# ProDoc_ChisFlash-Pichu.net
KiCad netlist of a schematic drawn in EasyEDA Pro
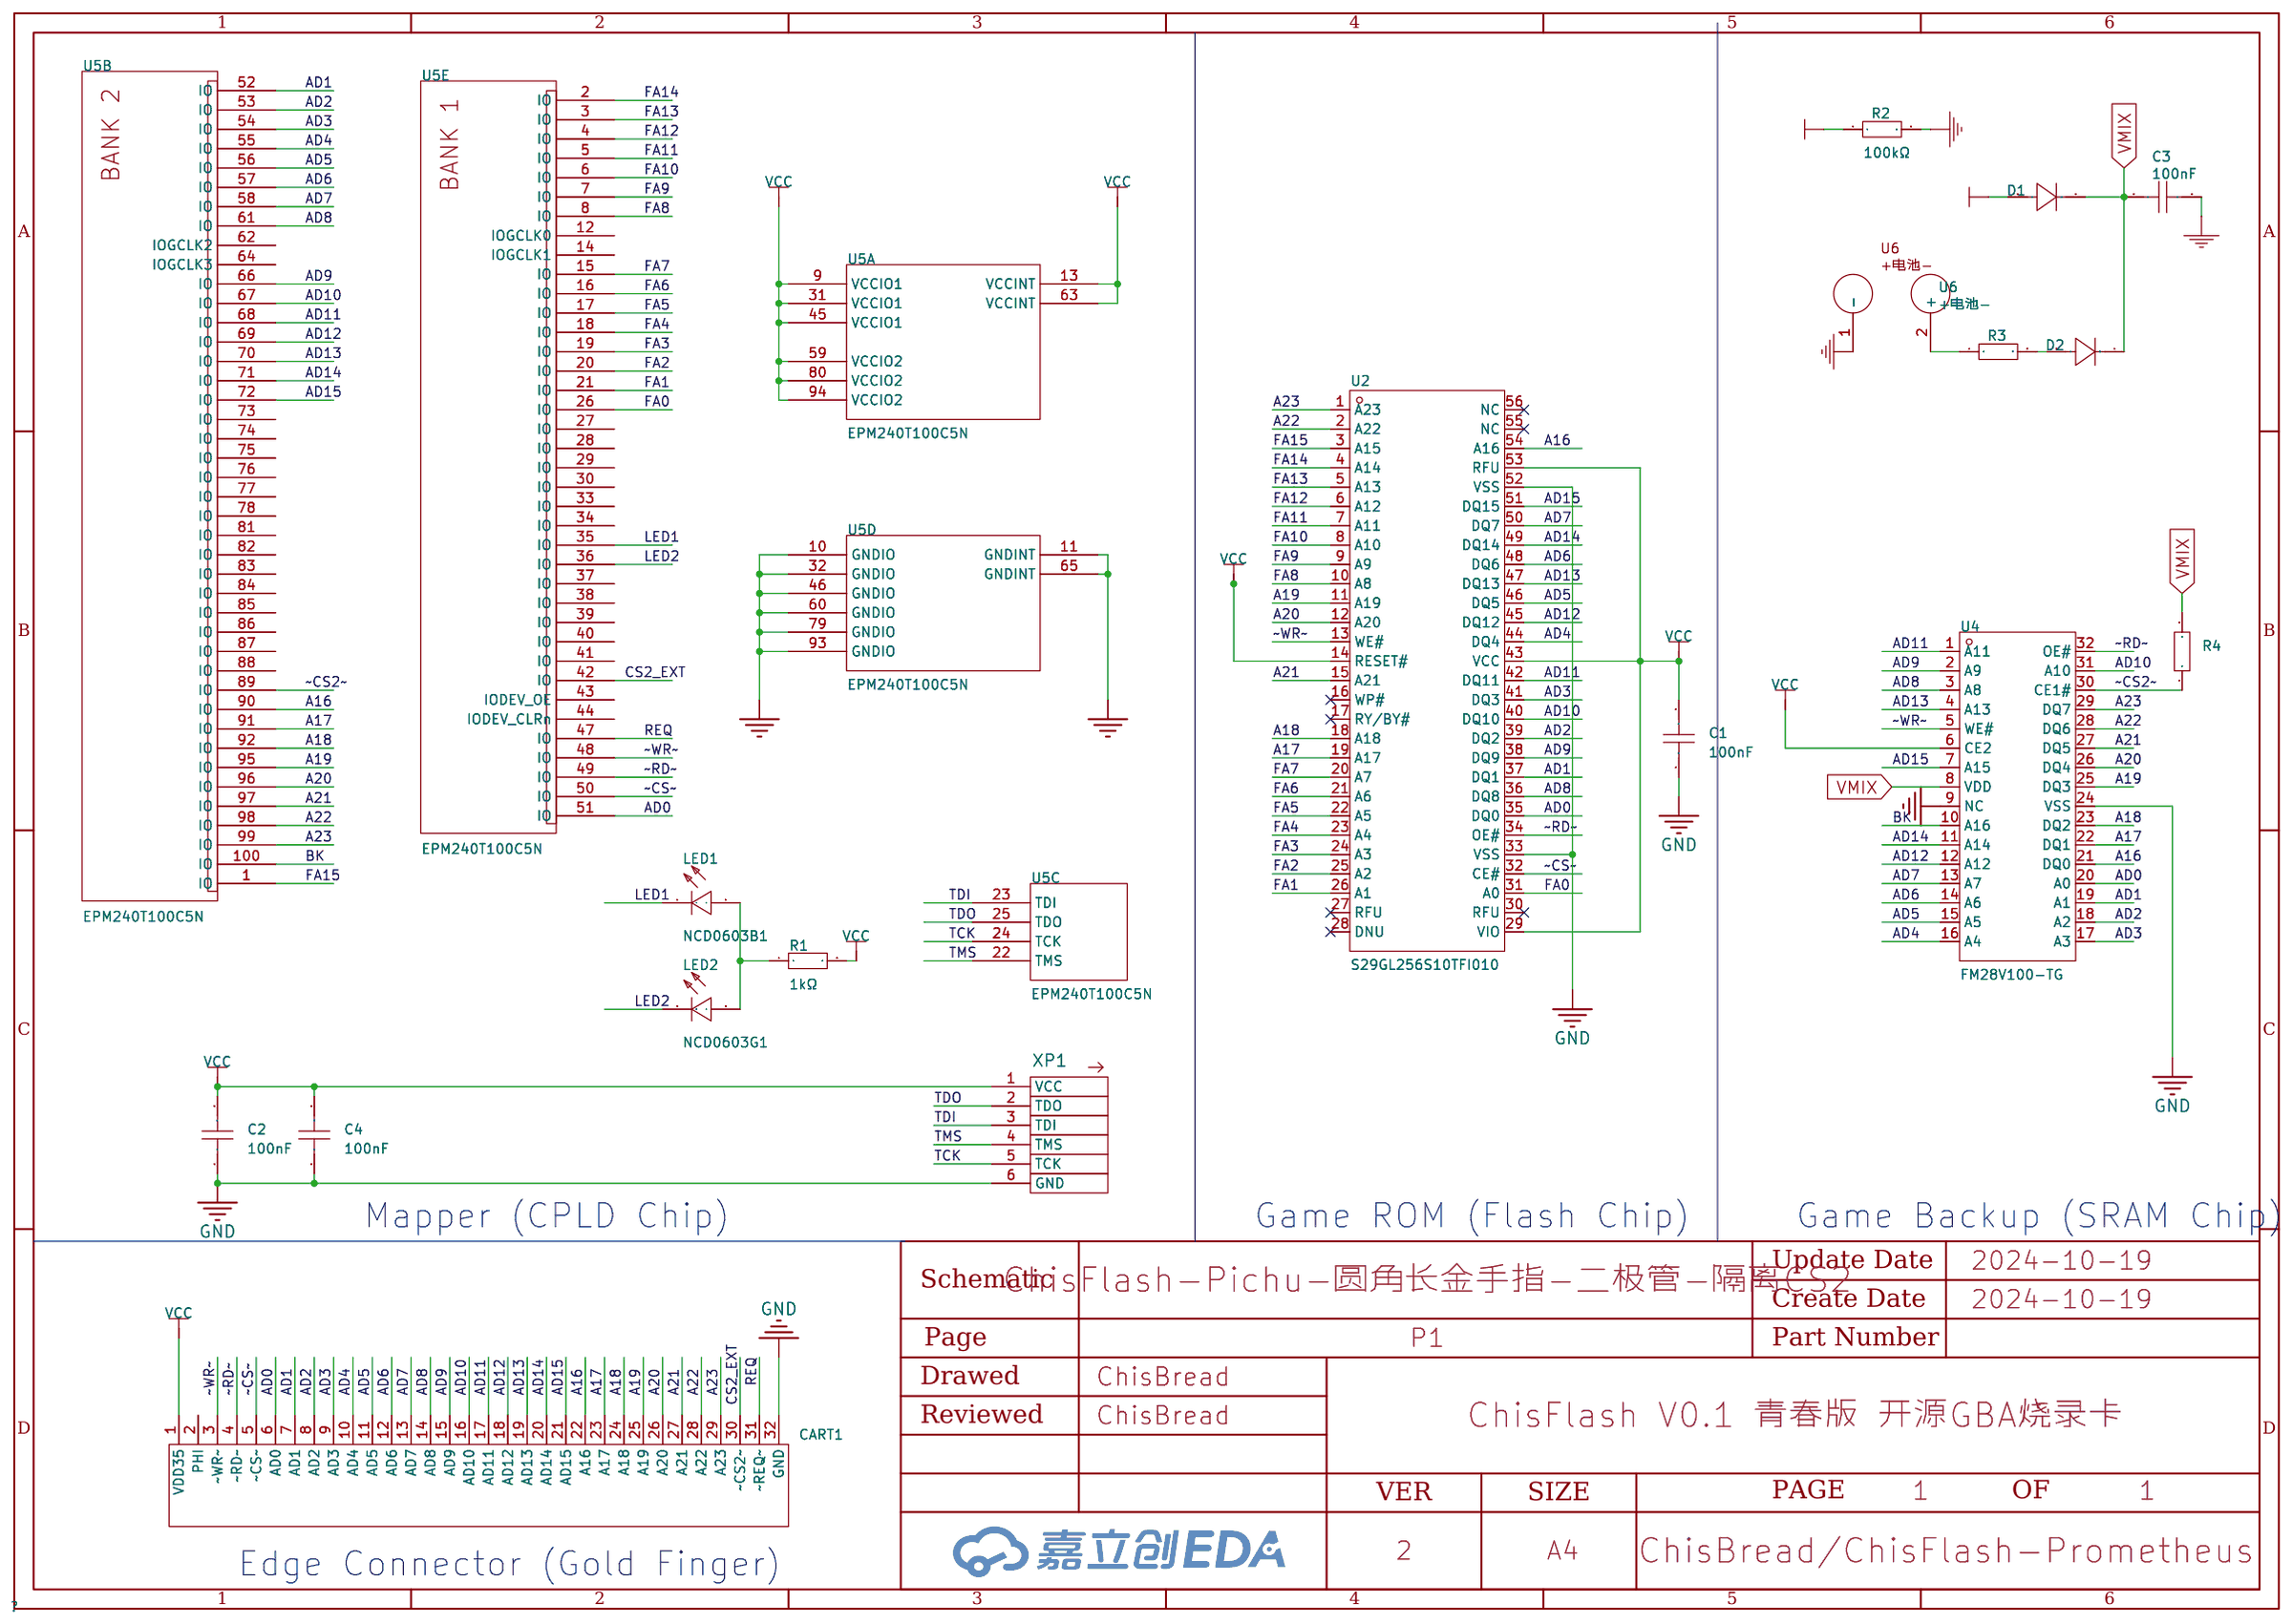
[diagram p0: schematic sheet]

(export (version "E")
  (design (tool "Eeschema 10.0.6"))
  (components
    (comp (ref "C1")
      (value "100nF")
      (footprint "easyedapro:C0603")
      (libsource (lib "easyedapro") (part "CapAcitance"))
    )
    (comp (ref "C2")
      (value "100nF")
      (footprint "easyedapro:C0603")
      (libsource (lib "easyedapro") (part "CapAcitance"))
    )
    (comp (ref "C3")
      (value "100nF")
      (footprint "easyedapro:C0603")
      (description "容值:100nF;精度:±10%;额定电压:50V;材质(温度系数):X7R;")
      (fields
        (field (name "Manufacturer Part") "CGA0603X7R104K500JT")
        (field (name "Manufacturer") "HRE(芯声)")
      )
      (libsource (lib "easyedapro") (part "CGA0603X7R104K500JT"))
    )
    (comp (ref "C4")
      (value "100nF")
      (footprint "easyedapro:C0603")
      (libsource (lib "easyedapro") (part "CapAcitance"))
    )
    (comp (ref "CART1")
      (value "~")
      (footprint "easyedapro:GBA卡带金手指")
      (description "GBA卡带金手指")
      (libsource (lib "easyedapro") (part "GBA卡带金手指"))
    )
    (comp (ref "D1")
      (value "1N4148WS")
      (footprint "easyedapro:SOD-323_L1.8-W1.3-LS2.5-RD")
      (description "二极管配置:独立式;正向压降(Vf):1.25V@150mA;直流反向耐压(Vr):100V;平均整流电流(Io):300mA;功率:400mW;反向恢复时间(trr):8ns;")
      (fields (field (name "Manufacturer") "JSMSEMI(杰盛微)"))
      (libsource (lib "easyedapro") (part "1N4148WS_C917117"))
    )
    (comp (ref "D2")
      (value "1N4148WS")
      (footprint "easyedapro:SOD-323_L1.8-W1.3-LS2.5-RD")
      (description "二极管配置:独立式;正向压降(Vf):1.25V@150mA;直流反向耐压(Vr):100V;平均整流电流(Io):300mA;功率:400mW;反向恢复时间(trr):8ns;")
      (fields (field (name "Manufacturer") "JSMSEMI(杰盛微)"))
      (libsource (lib "easyedapro") (part "1N4148WS_C917117"))
    )
    (comp (ref "LED1")
      (value "NCD0603B1")
      (footprint "easyedapro:LED0603-RD")
      (fields (field (name "Manufacturer") "国星光电"))
      (libsource (lib "easyedapro") (part "FC-DA1608BK-470H10"))
    )
    (comp (ref "LED2")
      (value "NCD0603G1")
      (footprint "easyedapro:LED0603-RD")
      (fields (field (name "Manufacturer") "国星光电"))
      (libsource (lib "easyedapro") (part "FC-D1608UGK-520D10"))
    )
    (comp (ref "R1")
      (value "1kΩ")
      (footprint "easyedapro:R0603")
      (description "电阻类型:厚膜电阻;阻值:1kΩ;精度:±1%;功率:100mW;最大工作电压:75V;温度系数:±100ppm/°C;")
      (fields
        (field (name "Manufacturer Part") "0603WAF1001T5E")
        (field (name "Manufacturer") "UNI-ROYAL(厚声)")
      )
      (libsource (lib "easyedapro") (part "0603WAF1001T5E"))
    )
    (comp (ref "R2")
      (value "100kΩ")
      (footprint "easyedapro:R0603")
      (description "电阻类型:厚膜电阻;阻值:100kΩ;精度:±1%;功率:100mW;最大工作电压:75V;温度系数:±100ppm/°C;")
      (fields
        (field (name "Manufacturer Part") "0603WAF1003T5E")
        (field (name "Manufacturer") "UNI-ROYAL(厚声)")
      )
      (libsource (lib "easyedapro") (part "0603WAF1003T5E"))
    )
    (comp (ref "R3")
      (value "10kΩ")
      (footprint "easyedapro:R0603")
      (description "电阻类型:厚膜电阻;阻值:10kΩ;精度:±1%;功率:100mW;最大工作电压:75V;温度系数:±100ppm/°C;")
      (fields
        (field (name "Manufacturer Part") "0603WAF1002T5E")
        (field (name "Manufacturer") "UNI-ROYAL(厚声)")
      )
      (libsource (lib "easyedapro") (part "0603WAF1002T5E"))
    )
    (comp (ref "R4")
      (value "10kΩ")
      (footprint "easyedapro:R0603")
      (description "电阻类型:厚膜电阻;阻值:10kΩ;精度:±1%;功率:100mW;最大工作电压:75V;温度系数:±100ppm/°C;")
      (fields
        (field (name "Manufacturer Part") "0603WAF1002T5E")
        (field (name "Manufacturer") "UNI-ROYAL(厚声)")
      )
      (libsource (lib "easyedapro") (part "0603WAF1002T5E"))
    )
    (comp (ref "U2")
      (value "S29GL256S10TFI010")
      (footprint "easyedapro:TSOP-56_L18.4-W14.0-P0.50-LS20.0-TL")
      (fields (field (name "Manufacturer") "SPANSION(飞索)"))
      (libsource (lib "easyedapro") (part "S29GL256S10TFI010"))
    )
    (comp (ref "U4")
      (value "FM28V100-TG")
      (fields (field (name "Manufacturer") "CYPRESS(赛普拉斯)"))
      (libsource (lib "easyedapro") (part "FM28V100-TG_C2959453"))
    )
    (comp (ref "U5")
      (value "EPM240T100C5N")
      (footprint "easyedapro:TQFP-100_L14.0-W14.0-P0.50-LS16.0-BL")
      (description "类型:其它PLD;逻辑门数量:-;逻辑单元数:-;逻辑阵列块数:240;")
      (fields (field (name "Manufacturer") "Intel/Altera"))
      (libsource (lib "easyedapro") (part "EPM240T100C5N"))
    )
    (comp (ref "U6")
      (value "+电池-")
      (footprint "easyedapro:电池2")
      (libsource (lib "easyedapro") (part "GBA烧录卡电池"))
    )
    (comp (ref "XP1")
      (value "JTAG")
      (footprint "easyedapro:HDR-TH_6P-P1.27-V-M-1")
      (libsource (lib "easyedapro") (part "jtag"))
    )
  )
  (nets
    (net (code "1") (name "/A16") (class "Default")
      (node (ref "CART1") (pin "22") (pinfunction "A16_22") (pintype "input"))
      (node (ref "U2") (pin "54") (pinfunction "A16_54") (pintype "input"))
      (node (ref "U4") (pin "21") (pinfunction "DQ0_21") (pintype "unspecified"))
      (node (ref "U5") (pin "90") (pinfunction "IO_90") (pintype "bidirectional"))
    )
    (net (code "2") (name "/A17") (class "Default")
      (node (ref "CART1") (pin "23") (pinfunction "A17_23") (pintype "input"))
      (node (ref "U2") (pin "19") (pinfunction "A17_19") (pintype "input"))
      (node (ref "U4") (pin "22") (pinfunction "DQ1_22") (pintype "unspecified"))
      (node (ref "U5") (pin "91") (pinfunction "IO_91") (pintype "bidirectional"))
    )
    (net (code "3") (name "/A18") (class "Default")
      (node (ref "CART1") (pin "24") (pinfunction "A18_24") (pintype "input"))
      (node (ref "U2") (pin "18") (pinfunction "A18_18") (pintype "input"))
      (node (ref "U4") (pin "23") (pinfunction "DQ2_23") (pintype "unspecified"))
      (node (ref "U5") (pin "92") (pinfunction "IO_92") (pintype "bidirectional"))
    )
    (net (code "4") (name "/A19") (class "Default")
      (node (ref "CART1") (pin "25") (pinfunction "A19_25") (pintype "input"))
      (node (ref "U2") (pin "11") (pinfunction "A19_11") (pintype "input"))
      (node (ref "U4") (pin "25") (pinfunction "DQ3_25") (pintype "unspecified"))
      (node (ref "U5") (pin "95") (pinfunction "IO_95") (pintype "bidirectional"))
    )
    (net (code "5") (name "/A20") (class "Default")
      (node (ref "CART1") (pin "26") (pinfunction "A20_26") (pintype "input"))
      (node (ref "U2") (pin "12") (pinfunction "A20_12") (pintype "input"))
      (node (ref "U4") (pin "26") (pinfunction "DQ4_26") (pintype "unspecified"))
      (node (ref "U5") (pin "96") (pinfunction "IO_96") (pintype "bidirectional"))
    )
    (net (code "6") (name "/A21") (class "Default")
      (node (ref "CART1") (pin "27") (pinfunction "A21_27") (pintype "input"))
      (node (ref "U2") (pin "15") (pinfunction "A21_15") (pintype "input"))
      (node (ref "U4") (pin "27") (pinfunction "DQ5_27") (pintype "unspecified"))
      (node (ref "U5") (pin "97") (pinfunction "IO_97") (pintype "bidirectional"))
    )
    (net (code "7") (name "/A22") (class "Default")
      (node (ref "CART1") (pin "28") (pinfunction "A22_28") (pintype "input"))
      (node (ref "U2") (pin "2") (pinfunction "A22_2") (pintype "input"))
      (node (ref "U4") (pin "28") (pinfunction "DQ6_28") (pintype "unspecified"))
      (node (ref "U5") (pin "98") (pinfunction "IO_98") (pintype "bidirectional"))
    )
    (net (code "8") (name "/A23") (class "Default")
      (node (ref "CART1") (pin "29") (pinfunction "A23_29") (pintype "input"))
      (node (ref "U2") (pin "1") (pinfunction "A23_1") (pintype "input"))
      (node (ref "U4") (pin "29") (pinfunction "DQ7_29") (pintype "unspecified"))
      (node (ref "U5") (pin "99") (pinfunction "IO_99") (pintype "bidirectional"))
    )
    (net (code "9") (name "/AD0") (class "Default")
      (node (ref "CART1") (pin "6") (pinfunction "AD0_6") (pintype "input"))
      (node (ref "U2") (pin "35") (pinfunction "DQ0_35") (pintype "input"))
      (node (ref "U4") (pin "20") (pinfunction "A0_20") (pintype "unspecified"))
      (node (ref "U5") (pin "51") (pinfunction "IO_51") (pintype "bidirectional"))
    )
    (net (code "10") (name "/AD1") (class "Default")
      (node (ref "CART1") (pin "7") (pinfunction "AD1_7") (pintype "input"))
      (node (ref "U2") (pin "37") (pinfunction "DQ1_37") (pintype "input"))
      (node (ref "U4") (pin "19") (pinfunction "A1_19") (pintype "unspecified"))
      (node (ref "U5") (pin "52") (pinfunction "IO_52") (pintype "bidirectional"))
    )
    (net (code "11") (name "/AD2") (class "Default")
      (node (ref "CART1") (pin "8") (pinfunction "AD2_8") (pintype "input"))
      (node (ref "U2") (pin "39") (pinfunction "DQ2_39") (pintype "input"))
      (node (ref "U4") (pin "18") (pinfunction "A2_18") (pintype "unspecified"))
      (node (ref "U5") (pin "53") (pinfunction "IO_53") (pintype "bidirectional"))
    )
    (net (code "12") (name "/AD3") (class "Default")
      (node (ref "CART1") (pin "9") (pinfunction "AD3_9") (pintype "input"))
      (node (ref "U2") (pin "41") (pinfunction "DQ3_41") (pintype "input"))
      (node (ref "U4") (pin "17") (pinfunction "A3_17") (pintype "unspecified"))
      (node (ref "U5") (pin "54") (pinfunction "IO_54") (pintype "bidirectional"))
    )
    (net (code "13") (name "/AD4") (class "Default")
      (node (ref "CART1") (pin "10") (pinfunction "AD4_10") (pintype "input"))
      (node (ref "U2") (pin "44") (pinfunction "DQ4_44") (pintype "input"))
      (node (ref "U4") (pin "16") (pinfunction "A4_16") (pintype "unspecified"))
      (node (ref "U5") (pin "55") (pinfunction "IO_55") (pintype "bidirectional"))
    )
    (net (code "14") (name "/AD5") (class "Default")
      (node (ref "CART1") (pin "11") (pinfunction "AD5_11") (pintype "input"))
      (node (ref "U2") (pin "46") (pinfunction "DQ5_46") (pintype "input"))
      (node (ref "U4") (pin "15") (pinfunction "A5_15") (pintype "unspecified"))
      (node (ref "U5") (pin "56") (pinfunction "IO_56") (pintype "bidirectional"))
    )
    (net (code "15") (name "/AD6") (class "Default")
      (node (ref "CART1") (pin "12") (pinfunction "AD6_12") (pintype "input"))
      (node (ref "U2") (pin "48") (pinfunction "DQ6_48") (pintype "input"))
      (node (ref "U4") (pin "14") (pinfunction "A6_14") (pintype "unspecified"))
      (node (ref "U5") (pin "57") (pinfunction "IO_57") (pintype "bidirectional"))
    )
    (net (code "16") (name "/AD7") (class "Default")
      (node (ref "CART1") (pin "13") (pinfunction "AD7_13") (pintype "input"))
      (node (ref "U2") (pin "50") (pinfunction "DQ7_50") (pintype "input"))
      (node (ref "U4") (pin "13") (pinfunction "A7_13") (pintype "unspecified"))
      (node (ref "U5") (pin "58") (pinfunction "IO_58") (pintype "bidirectional"))
    )
    (net (code "17") (name "/AD8") (class "Default")
      (node (ref "CART1") (pin "14") (pinfunction "AD8_14") (pintype "input"))
      (node (ref "U2") (pin "36") (pinfunction "DQ8_36") (pintype "input"))
      (node (ref "U4") (pin "3") (pinfunction "A8_3") (pintype "unspecified"))
      (node (ref "U5") (pin "61") (pinfunction "IO_61") (pintype "bidirectional"))
    )
    (net (code "18") (name "/AD9") (class "Default")
      (node (ref "CART1") (pin "15") (pinfunction "AD9_15") (pintype "input"))
      (node (ref "U2") (pin "38") (pinfunction "DQ9_38") (pintype "input"))
      (node (ref "U4") (pin "2") (pinfunction "A9_2") (pintype "unspecified"))
      (node (ref "U5") (pin "66") (pinfunction "IO_66") (pintype "bidirectional"))
    )
    (net (code "19") (name "/AD10") (class "Default")
      (node (ref "CART1") (pin "16") (pinfunction "AD10_16") (pintype "input"))
      (node (ref "U2") (pin "40") (pinfunction "DQ10_40") (pintype "input"))
      (node (ref "U4") (pin "31") (pinfunction "A10_31") (pintype "unspecified"))
      (node (ref "U5") (pin "67") (pinfunction "IO_67") (pintype "bidirectional"))
    )
    (net (code "20") (name "/AD11") (class "Default")
      (node (ref "CART1") (pin "17") (pinfunction "AD11_17") (pintype "input"))
      (node (ref "U2") (pin "42") (pinfunction "DQ11_42") (pintype "input"))
      (node (ref "U4") (pin "1") (pinfunction "A11_1") (pintype "unspecified"))
      (node (ref "U5") (pin "68") (pinfunction "IO_68") (pintype "bidirectional"))
    )
    (net (code "21") (name "/AD12") (class "Default")
      (node (ref "CART1") (pin "18") (pinfunction "AD12_18") (pintype "input"))
      (node (ref "U2") (pin "45") (pinfunction "DQ12_45") (pintype "input"))
      (node (ref "U4") (pin "12") (pinfunction "A12_12") (pintype "unspecified"))
      (node (ref "U5") (pin "69") (pinfunction "IO_69") (pintype "bidirectional"))
    )
    (net (code "22") (name "/AD13") (class "Default")
      (node (ref "CART1") (pin "19") (pinfunction "AD13_19") (pintype "input"))
      (node (ref "U2") (pin "47") (pinfunction "DQ13_47") (pintype "input"))
      (node (ref "U4") (pin "4") (pinfunction "A13_4") (pintype "unspecified"))
      (node (ref "U5") (pin "70") (pinfunction "IO_70") (pintype "bidirectional"))
    )
    (net (code "23") (name "/AD14") (class "Default")
      (node (ref "CART1") (pin "20") (pinfunction "AD14_20") (pintype "input"))
      (node (ref "U2") (pin "49") (pinfunction "DQ14_49") (pintype "input"))
      (node (ref "U4") (pin "11") (pinfunction "A14_11") (pintype "unspecified"))
      (node (ref "U5") (pin "71") (pinfunction "IO_71") (pintype "bidirectional"))
    )
    (net (code "24") (name "/AD15") (class "Default")
      (node (ref "CART1") (pin "21") (pinfunction "AD15_21") (pintype "input"))
      (node (ref "U2") (pin "51") (pinfunction "DQ15_51") (pintype "input"))
      (node (ref "U4") (pin "7") (pinfunction "A15_7") (pintype "unspecified"))
      (node (ref "U5") (pin "72") (pinfunction "IO_72") (pintype "bidirectional"))
    )
    (net (code "25") (name "/BK") (class "Default")
      (node (ref "U4") (pin "10") (pinfunction "A16_10") (pintype "unspecified"))
      (node (ref "U5") (pin "100") (pinfunction "IO_100") (pintype "bidirectional"))
    )
    (net (code "26") (name "/CS2_EXT") (class "Default")
      (node (ref "CART1") (pin "30") (pinfunction "~CS2~_30") (pintype "input"))
      (node (ref "U5") (pin "42") (pinfunction "IO_42") (pintype "bidirectional"))
    )
    (net (code "27") (name "/FA0") (class "Default")
      (node (ref "U2") (pin "31") (pinfunction "A0_31") (pintype "input"))
      (node (ref "U5") (pin "26") (pinfunction "IO_26") (pintype "bidirectional"))
    )
    (net (code "28") (name "/FA1") (class "Default")
      (node (ref "U2") (pin "26") (pinfunction "A1_26") (pintype "input"))
      (node (ref "U5") (pin "21") (pinfunction "IO_21") (pintype "bidirectional"))
    )
    (net (code "29") (name "/FA2") (class "Default")
      (node (ref "U2") (pin "25") (pinfunction "A2_25") (pintype "input"))
      (node (ref "U5") (pin "20") (pinfunction "IO_20") (pintype "bidirectional"))
    )
    (net (code "30") (name "/FA3") (class "Default")
      (node (ref "U2") (pin "24") (pinfunction "A3_24") (pintype "input"))
      (node (ref "U5") (pin "19") (pinfunction "IO_19") (pintype "bidirectional"))
    )
    (net (code "31") (name "/FA4") (class "Default")
      (node (ref "U2") (pin "23") (pinfunction "A4_23") (pintype "input"))
      (node (ref "U5") (pin "18") (pinfunction "IO_18") (pintype "bidirectional"))
    )
    (net (code "32") (name "/FA5") (class "Default")
      (node (ref "U2") (pin "22") (pinfunction "A5_22") (pintype "input"))
      (node (ref "U5") (pin "17") (pinfunction "IO_17") (pintype "bidirectional"))
    )
    (net (code "33") (name "/FA6") (class "Default")
      (node (ref "U2") (pin "21") (pinfunction "A6_21") (pintype "input"))
      (node (ref "U5") (pin "16") (pinfunction "IO_16") (pintype "bidirectional"))
    )
    (net (code "34") (name "/FA7") (class "Default")
      (node (ref "U2") (pin "20") (pinfunction "A7_20") (pintype "input"))
      (node (ref "U5") (pin "15") (pinfunction "IO_15") (pintype "bidirectional"))
    )
    (net (code "35") (name "/FA8") (class "Default")
      (node (ref "U2") (pin "10") (pinfunction "A8_10") (pintype "input"))
      (node (ref "U5") (pin "8") (pinfunction "IO_8") (pintype "bidirectional"))
    )
    (net (code "36") (name "/FA9") (class "Default")
      (node (ref "U2") (pin "9") (pinfunction "A9_9") (pintype "input"))
      (node (ref "U5") (pin "7") (pinfunction "IO_7") (pintype "bidirectional"))
    )
    (net (code "37") (name "/FA10") (class "Default")
      (node (ref "U2") (pin "8") (pinfunction "A10_8") (pintype "input"))
      (node (ref "U5") (pin "6") (pinfunction "IO_6") (pintype "bidirectional"))
    )
    (net (code "38") (name "/FA11") (class "Default")
      (node (ref "U2") (pin "7") (pinfunction "A11_7") (pintype "input"))
      (node (ref "U5") (pin "5") (pinfunction "IO_5") (pintype "bidirectional"))
    )
    (net (code "39") (name "/FA12") (class "Default")
      (node (ref "U2") (pin "6") (pinfunction "A12_6") (pintype "input"))
      (node (ref "U5") (pin "4") (pinfunction "IO_4") (pintype "bidirectional"))
    )
    (net (code "40") (name "/FA13") (class "Default")
      (node (ref "U2") (pin "5") (pinfunction "A13_5") (pintype "input"))
      (node (ref "U5") (pin "3") (pinfunction "IO_3") (pintype "bidirectional"))
    )
    (net (code "41") (name "/FA14") (class "Default")
      (node (ref "U2") (pin "4") (pinfunction "A14_4") (pintype "input"))
      (node (ref "U5") (pin "2") (pinfunction "IO_2") (pintype "bidirectional"))
    )
    (net (code "42") (name "/FA15") (class "Default")
      (node (ref "U2") (pin "3") (pinfunction "A15_3") (pintype "input"))
      (node (ref "U5") (pin "1") (pinfunction "IO_1") (pintype "bidirectional"))
    )
    (net (code "43") (name "/LED1") (class "Default")
      (node (ref "LED1") (pin "1") (pinfunction "-_1") (pintype "input"))
      (node (ref "U5") (pin "35") (pinfunction "IO_35") (pintype "bidirectional"))
    )
    (net (code "44") (name "/LED2") (class "Default")
      (node (ref "LED2") (pin "1") (pinfunction "K_1") (pintype "input"))
      (node (ref "U5") (pin "36") (pinfunction "IO_36") (pintype "bidirectional"))
    )
    (net (code "45") (name "/REQ") (class "Default")
      (node (ref "CART1") (pin "31") (pinfunction "~REQ~_31") (pintype "input"))
      (node (ref "U5") (pin "47") (pinfunction "IO_47") (pintype "bidirectional"))
    )
    (net (code "46") (name "/TCK") (class "Default")
      (node (ref "U5") (pin "24") (pinfunction "TCK_24") (pintype "unspecified"))
      (node (ref "XP1") (pin "5") (pinfunction "TCK_5") (pintype "input"))
    )
    (net (code "47") (name "/TDI") (class "Default")
      (node (ref "U5") (pin "23") (pinfunction "TDI_23") (pintype "unspecified"))
      (node (ref "XP1") (pin "3") (pinfunction "TDI_3") (pintype "output"))
    )
    (net (code "48") (name "/TDO") (class "Default")
      (node (ref "U5") (pin "25") (pinfunction "TDO_25") (pintype "output"))
      (node (ref "XP1") (pin "2") (pinfunction "TDO_2") (pintype "output"))
    )
    (net (code "49") (name "/TMS") (class "Default")
      (node (ref "U5") (pin "22") (pinfunction "TMS_22") (pintype "unspecified"))
      (node (ref "XP1") (pin "4") (pinfunction "TMS_4") (pintype "output"))
    )
    (net (code "50") (name "/~CS2~") (class "Default")
      (node (ref "R4") (pin "1") (pinfunction "1_1") (pintype "input"))
      (node (ref "U4") (pin "30") (pinfunction "CE1#_30") (pintype "unspecified"))
      (node (ref "U5") (pin "89") (pinfunction "IO_89") (pintype "bidirectional"))
    )
    (net (code "51") (name "/~CS~") (class "Default")
      (node (ref "CART1") (pin "5") (pinfunction "~CS~_5") (pintype "input"))
      (node (ref "U2") (pin "32") (pinfunction "CE#_32") (pintype "input"))
      (node (ref "U5") (pin "50") (pinfunction "IO_50") (pintype "bidirectional"))
    )
    (net (code "52") (name "/~RD~") (class "Default")
      (node (ref "CART1") (pin "4") (pinfunction "~RD~_4") (pintype "input"))
      (node (ref "U2") (pin "34") (pinfunction "OE#_34") (pintype "input"))
      (node (ref "U4") (pin "32") (pinfunction "OE#_32") (pintype "unspecified"))
      (node (ref "U5") (pin "49") (pinfunction "IO_49") (pintype "bidirectional"))
    )
    (net (code "53") (name "/~WR~") (class "Default")
      (node (ref "CART1") (pin "3") (pinfunction "~WR~_3") (pintype "input"))
      (node (ref "U2") (pin "13") (pinfunction "WE#_13") (pintype "input"))
      (node (ref "U4") (pin "5") (pinfunction "WE#_5") (pintype "unspecified"))
      (node (ref "U5") (pin "48") (pinfunction "IO_48") (pintype "bidirectional"))
    )
    (net (code "54") (name "GND") (class "Default")
      (node (ref "C1") (pin "1") (pinfunction "1_1") (pintype "input"))
      (node (ref "C2") (pin "1") (pinfunction "1_1") (pintype "input"))
      (node (ref "C3") (pin "2") (pinfunction "2_2") (pintype "unspecified"))
      (node (ref "C4") (pin "1") (pinfunction "1_1") (pintype "input"))
      (node (ref "CART1") (pin "32") (pinfunction "GND_32") (pintype "input"))
      (node (ref "R2") (pin "2") (pinfunction "2_2") (pintype "input"))
      (node (ref "U2") (pin "33") (pinfunction "VSS_33") (pintype "input"))
      (node (ref "U2") (pin "52") (pinfunction "VSS_52") (pintype "input"))
      (node (ref "U4") (pin "24") (pinfunction "VSS_24") (pintype "unspecified"))
      (node (ref "U4") (pin "9") (pinfunction "NC_9") (pintype "unspecified"))
      (node (ref "U5") (pin "10") (pinfunction "GNDIO_10") (pintype "unspecified"))
      (node (ref "U5") (pin "11") (pinfunction "GNDINT_11") (pintype "unspecified"))
      (node (ref "U5") (pin "32") (pinfunction "GNDIO_32") (pintype "unspecified"))
      (node (ref "U5") (pin "46") (pinfunction "GNDIO_46") (pintype "unspecified"))
      (node (ref "U5") (pin "60") (pinfunction "GNDIO_60") (pintype "unspecified"))
      (node (ref "U5") (pin "65") (pinfunction "GNDINT_65") (pintype "unspecified"))
      (node (ref "U5") (pin "79") (pinfunction "GNDIO_79") (pintype "unspecified"))
      (node (ref "U5") (pin "93") (pinfunction "GNDIO_93") (pintype "unspecified"))
      (node (ref "U6") (pin "1") (pinfunction "-_1") (pintype "unspecified"))
      (node (ref "XP1") (pin "6") (pinfunction "GND_6") (pintype "input"))
    )
    (net (code "55") (name "Net-(D2-A)") (class "Default")
      (node (ref "D2") (pin "2") (pinfunction "A_2") (pintype "unspecified"))
      (node (ref "R3") (pin "2") (pinfunction "2_2") (pintype "input"))
    )
    (net (code "56") (name "Net-(LED1-+)") (class "Default")
      (node (ref "LED1") (pin "2") (pinfunction "+_2") (pintype "input"))
      (node (ref "LED2") (pin "2") (pinfunction "A_2") (pintype "input"))
      (node (ref "R1") (pin "1") (pinfunction "1_1") (pintype "input"))
    )
    (net (code "57") (name "Net-(U6-+)") (class "Default")
      (node (ref "R3") (pin "1") (pinfunction "1_1") (pintype "input"))
      (node (ref "U6") (pin "2") (pinfunction "+_2") (pintype "unspecified"))
    )
    (net (code "58") (name "VCC") (class "Default")
      (node (ref "C1") (pin "2") (pinfunction "2_2") (pintype "input"))
      (node (ref "C2") (pin "2") (pinfunction "2_2") (pintype "input"))
      (node (ref "C4") (pin "2") (pinfunction "2_2") (pintype "input"))
      (node (ref "CART1") (pin "1") (pinfunction "VDD35_1") (pintype "input"))
      (node (ref "D1") (pin "2") (pinfunction "A_2") (pintype "unspecified"))
      (node (ref "R1") (pin "2") (pinfunction "2_2") (pintype "input"))
      (node (ref "R2") (pin "1") (pinfunction "1_1") (pintype "input"))
      (node (ref "U2") (pin "14") (pinfunction "RESET#_14") (pintype "input"))
      (node (ref "U2") (pin "29") (pinfunction "VIO_29") (pintype "input"))
      (node (ref "U2") (pin "43") (pinfunction "VCC_43") (pintype "input"))
      (node (ref "U2") (pin "53") (pinfunction "RFU_53") (pintype "input"))
      (node (ref "U4") (pin "6") (pinfunction "CE2_6") (pintype "unspecified"))
      (node (ref "U5") (pin "13") (pinfunction "VCCINT_13") (pintype "unspecified"))
      (node (ref "U5") (pin "31") (pinfunction "VCCIO1_31") (pintype "unspecified"))
      (node (ref "U5") (pin "45") (pinfunction "VCCIO1_45") (pintype "unspecified"))
      (node (ref "U5") (pin "59") (pinfunction "VCCIO2_59") (pintype "unspecified"))
      (node (ref "U5") (pin "63") (pinfunction "VCCINT_63") (pintype "unspecified"))
      (node (ref "U5") (pin "80") (pinfunction "VCCIO2_80") (pintype "unspecified"))
      (node (ref "U5") (pin "9") (pinfunction "VCCIO1_9") (pintype "unspecified"))
      (node (ref "U5") (pin "94") (pinfunction "VCCIO2_94") (pintype "unspecified"))
      (node (ref "XP1") (pin "1") (pinfunction "VCC_1") (pintype "output"))
    )
    (net (code "59") (name "VMIX") (class "Default")
      (node (ref "C3") (pin "1") (pinfunction "1_1") (pintype "unspecified"))
      (node (ref "D1") (pin "1") (pinfunction "C_1") (pintype "unspecified"))
      (node (ref "D2") (pin "1") (pinfunction "C_1") (pintype "unspecified"))
      (node (ref "R4") (pin "2") (pinfunction "2_2") (pintype "input"))
      (node (ref "U4") (pin "8") (pinfunction "VDD_8") (pintype "unspecified"))
    )
    (net (code "60") (name "unconnected-(CART1-PHI-Pad2)") (class "Default")
      (node (ref "CART1") (pin "2") (pinfunction "PHI_2") (pintype "input"))
    )
    (net (code "61") (name "unconnected-(U2-DNU-Pad28)") (class "Default")
      (node (ref "U2") (pin "28") (pinfunction "DNU_28") (pintype "input+no_connect"))
    )
    (net (code "62") (name "unconnected-(U2-NC-Pad55)") (class "Default")
      (node (ref "U2") (pin "55") (pinfunction "NC_55") (pintype "input+no_connect"))
    )
    (net (code "63") (name "unconnected-(U2-NC-Pad56)") (class "Default")
      (node (ref "U2") (pin "56") (pinfunction "NC_56") (pintype "input+no_connect"))
    )
    (net (code "64") (name "unconnected-(U2-RFU-Pad27)") (class "Default")
      (node (ref "U2") (pin "27") (pinfunction "RFU_27") (pintype "input+no_connect"))
    )
    (net (code "65") (name "unconnected-(U2-RFU-Pad30)") (class "Default")
      (node (ref "U2") (pin "30") (pinfunction "RFU_30") (pintype "input+no_connect"))
    )
    (net (code "66") (name "unconnected-(U2-RY{slash}BY#-Pad17)") (class "Default")
      (node (ref "U2") (pin "17") (pinfunction "RY/BY#_17") (pintype "input+no_connect"))
    )
    (net (code "67") (name "unconnected-(U2-WP#-Pad16)") (class "Default")
      (node (ref "U2") (pin "16") (pinfunction "WP#_16") (pintype "input+no_connect"))
    )
    (net (code "68") (name "unconnected-(U5B-IO-Pad73)") (class "Default")
      (node (ref "U5") (pin "73") (pinfunction "IO_73") (pintype "bidirectional"))
    )
    (net (code "69") (name "unconnected-(U5B-IO-Pad74)") (class "Default")
      (node (ref "U5") (pin "74") (pinfunction "IO_74") (pintype "bidirectional"))
    )
    (net (code "70") (name "unconnected-(U5B-IO-Pad75)") (class "Default")
      (node (ref "U5") (pin "75") (pinfunction "IO_75") (pintype "bidirectional"))
    )
    (net (code "71") (name "unconnected-(U5B-IO-Pad76)") (class "Default")
      (node (ref "U5") (pin "76") (pinfunction "IO_76") (pintype "bidirectional"))
    )
    (net (code "72") (name "unconnected-(U5B-IO-Pad77)") (class "Default")
      (node (ref "U5") (pin "77") (pinfunction "IO_77") (pintype "bidirectional"))
    )
    (net (code "73") (name "unconnected-(U5B-IO-Pad78)") (class "Default")
      (node (ref "U5") (pin "78") (pinfunction "IO_78") (pintype "bidirectional"))
    )
    (net (code "74") (name "unconnected-(U5B-IO-Pad81)") (class "Default")
      (node (ref "U5") (pin "81") (pinfunction "IO_81") (pintype "bidirectional"))
    )
    (net (code "75") (name "unconnected-(U5B-IO-Pad82)") (class "Default")
      (node (ref "U5") (pin "82") (pinfunction "IO_82") (pintype "bidirectional"))
    )
    (net (code "76") (name "unconnected-(U5B-IO-Pad83)") (class "Default")
      (node (ref "U5") (pin "83") (pinfunction "IO_83") (pintype "bidirectional"))
    )
    (net (code "77") (name "unconnected-(U5B-IO-Pad84)") (class "Default")
      (node (ref "U5") (pin "84") (pinfunction "IO_84") (pintype "bidirectional"))
    )
    (net (code "78") (name "unconnected-(U5B-IO-Pad85)") (class "Default")
      (node (ref "U5") (pin "85") (pinfunction "IO_85") (pintype "bidirectional"))
    )
    (net (code "79") (name "unconnected-(U5B-IO-Pad86)") (class "Default")
      (node (ref "U5") (pin "86") (pinfunction "IO_86") (pintype "bidirectional"))
    )
    (net (code "80") (name "unconnected-(U5B-IO-Pad87)") (class "Default")
      (node (ref "U5") (pin "87") (pinfunction "IO_87") (pintype "bidirectional"))
    )
    (net (code "81") (name "unconnected-(U5B-IO-Pad88)") (class "Default")
      (node (ref "U5") (pin "88") (pinfunction "IO_88") (pintype "bidirectional"))
    )
    (net (code "82") (name "unconnected-(U5B-IOGCLK2-Pad62)") (class "Default")
      (node (ref "U5") (pin "62") (pinfunction "IOGCLK2_62") (pintype "bidirectional"))
    )
    (net (code "83") (name "unconnected-(U5B-IOGCLK3-Pad64)") (class "Default")
      (node (ref "U5") (pin "64") (pinfunction "IOGCLK3_64") (pintype "bidirectional"))
    )
    (net (code "84") (name "unconnected-(U5E-IO-Pad27)") (class "Default")
      (node (ref "U5") (pin "27") (pinfunction "IO_27") (pintype "bidirectional"))
    )
    (net (code "85") (name "unconnected-(U5E-IO-Pad28)") (class "Default")
      (node (ref "U5") (pin "28") (pinfunction "IO_28") (pintype "bidirectional"))
    )
    (net (code "86") (name "unconnected-(U5E-IO-Pad29)") (class "Default")
      (node (ref "U5") (pin "29") (pinfunction "IO_29") (pintype "bidirectional"))
    )
    (net (code "87") (name "unconnected-(U5E-IO-Pad30)") (class "Default")
      (node (ref "U5") (pin "30") (pinfunction "IO_30") (pintype "bidirectional"))
    )
    (net (code "88") (name "unconnected-(U5E-IO-Pad33)") (class "Default")
      (node (ref "U5") (pin "33") (pinfunction "IO_33") (pintype "bidirectional"))
    )
    (net (code "89") (name "unconnected-(U5E-IO-Pad34)") (class "Default")
      (node (ref "U5") (pin "34") (pinfunction "IO_34") (pintype "bidirectional"))
    )
    (net (code "90") (name "unconnected-(U5E-IO-Pad37)") (class "Default")
      (node (ref "U5") (pin "37") (pinfunction "IO_37") (pintype "bidirectional"))
    )
    (net (code "91") (name "unconnected-(U5E-IO-Pad38)") (class "Default")
      (node (ref "U5") (pin "38") (pinfunction "IO_38") (pintype "bidirectional"))
    )
    (net (code "92") (name "unconnected-(U5E-IO-Pad39)") (class "Default")
      (node (ref "U5") (pin "39") (pinfunction "IO_39") (pintype "bidirectional"))
    )
    (net (code "93") (name "unconnected-(U5E-IO-Pad40)") (class "Default")
      (node (ref "U5") (pin "40") (pinfunction "IO_40") (pintype "bidirectional"))
    )
    (net (code "94") (name "unconnected-(U5E-IO-Pad41)") (class "Default")
      (node (ref "U5") (pin "41") (pinfunction "IO_41") (pintype "bidirectional"))
    )
    (net (code "95") (name "unconnected-(U5E-IODEV_CLRn-Pad44)") (class "Default")
      (node (ref "U5") (pin "44") (pinfunction "IODEV_CLRn_44") (pintype "bidirectional"))
    )
    (net (code "96") (name "unconnected-(U5E-IODEV_OE-Pad43)") (class "Default")
      (node (ref "U5") (pin "43") (pinfunction "IODEV_OE_43") (pintype "bidirectional"))
    )
    (net (code "97") (name "unconnected-(U5E-IOGCLK0-Pad12)") (class "Default")
      (node (ref "U5") (pin "12") (pinfunction "IOGCLK0_12") (pintype "bidirectional"))
    )
    (net (code "98") (name "unconnected-(U5E-IOGCLK1-Pad14)") (class "Default")
      (node (ref "U5") (pin "14") (pinfunction "IOGCLK1_14") (pintype "bidirectional"))
    )
  )
)
